# SCH_IoTNode_2025-08-17.net
KiCad netlist of a schematic drawn in EasyEDA
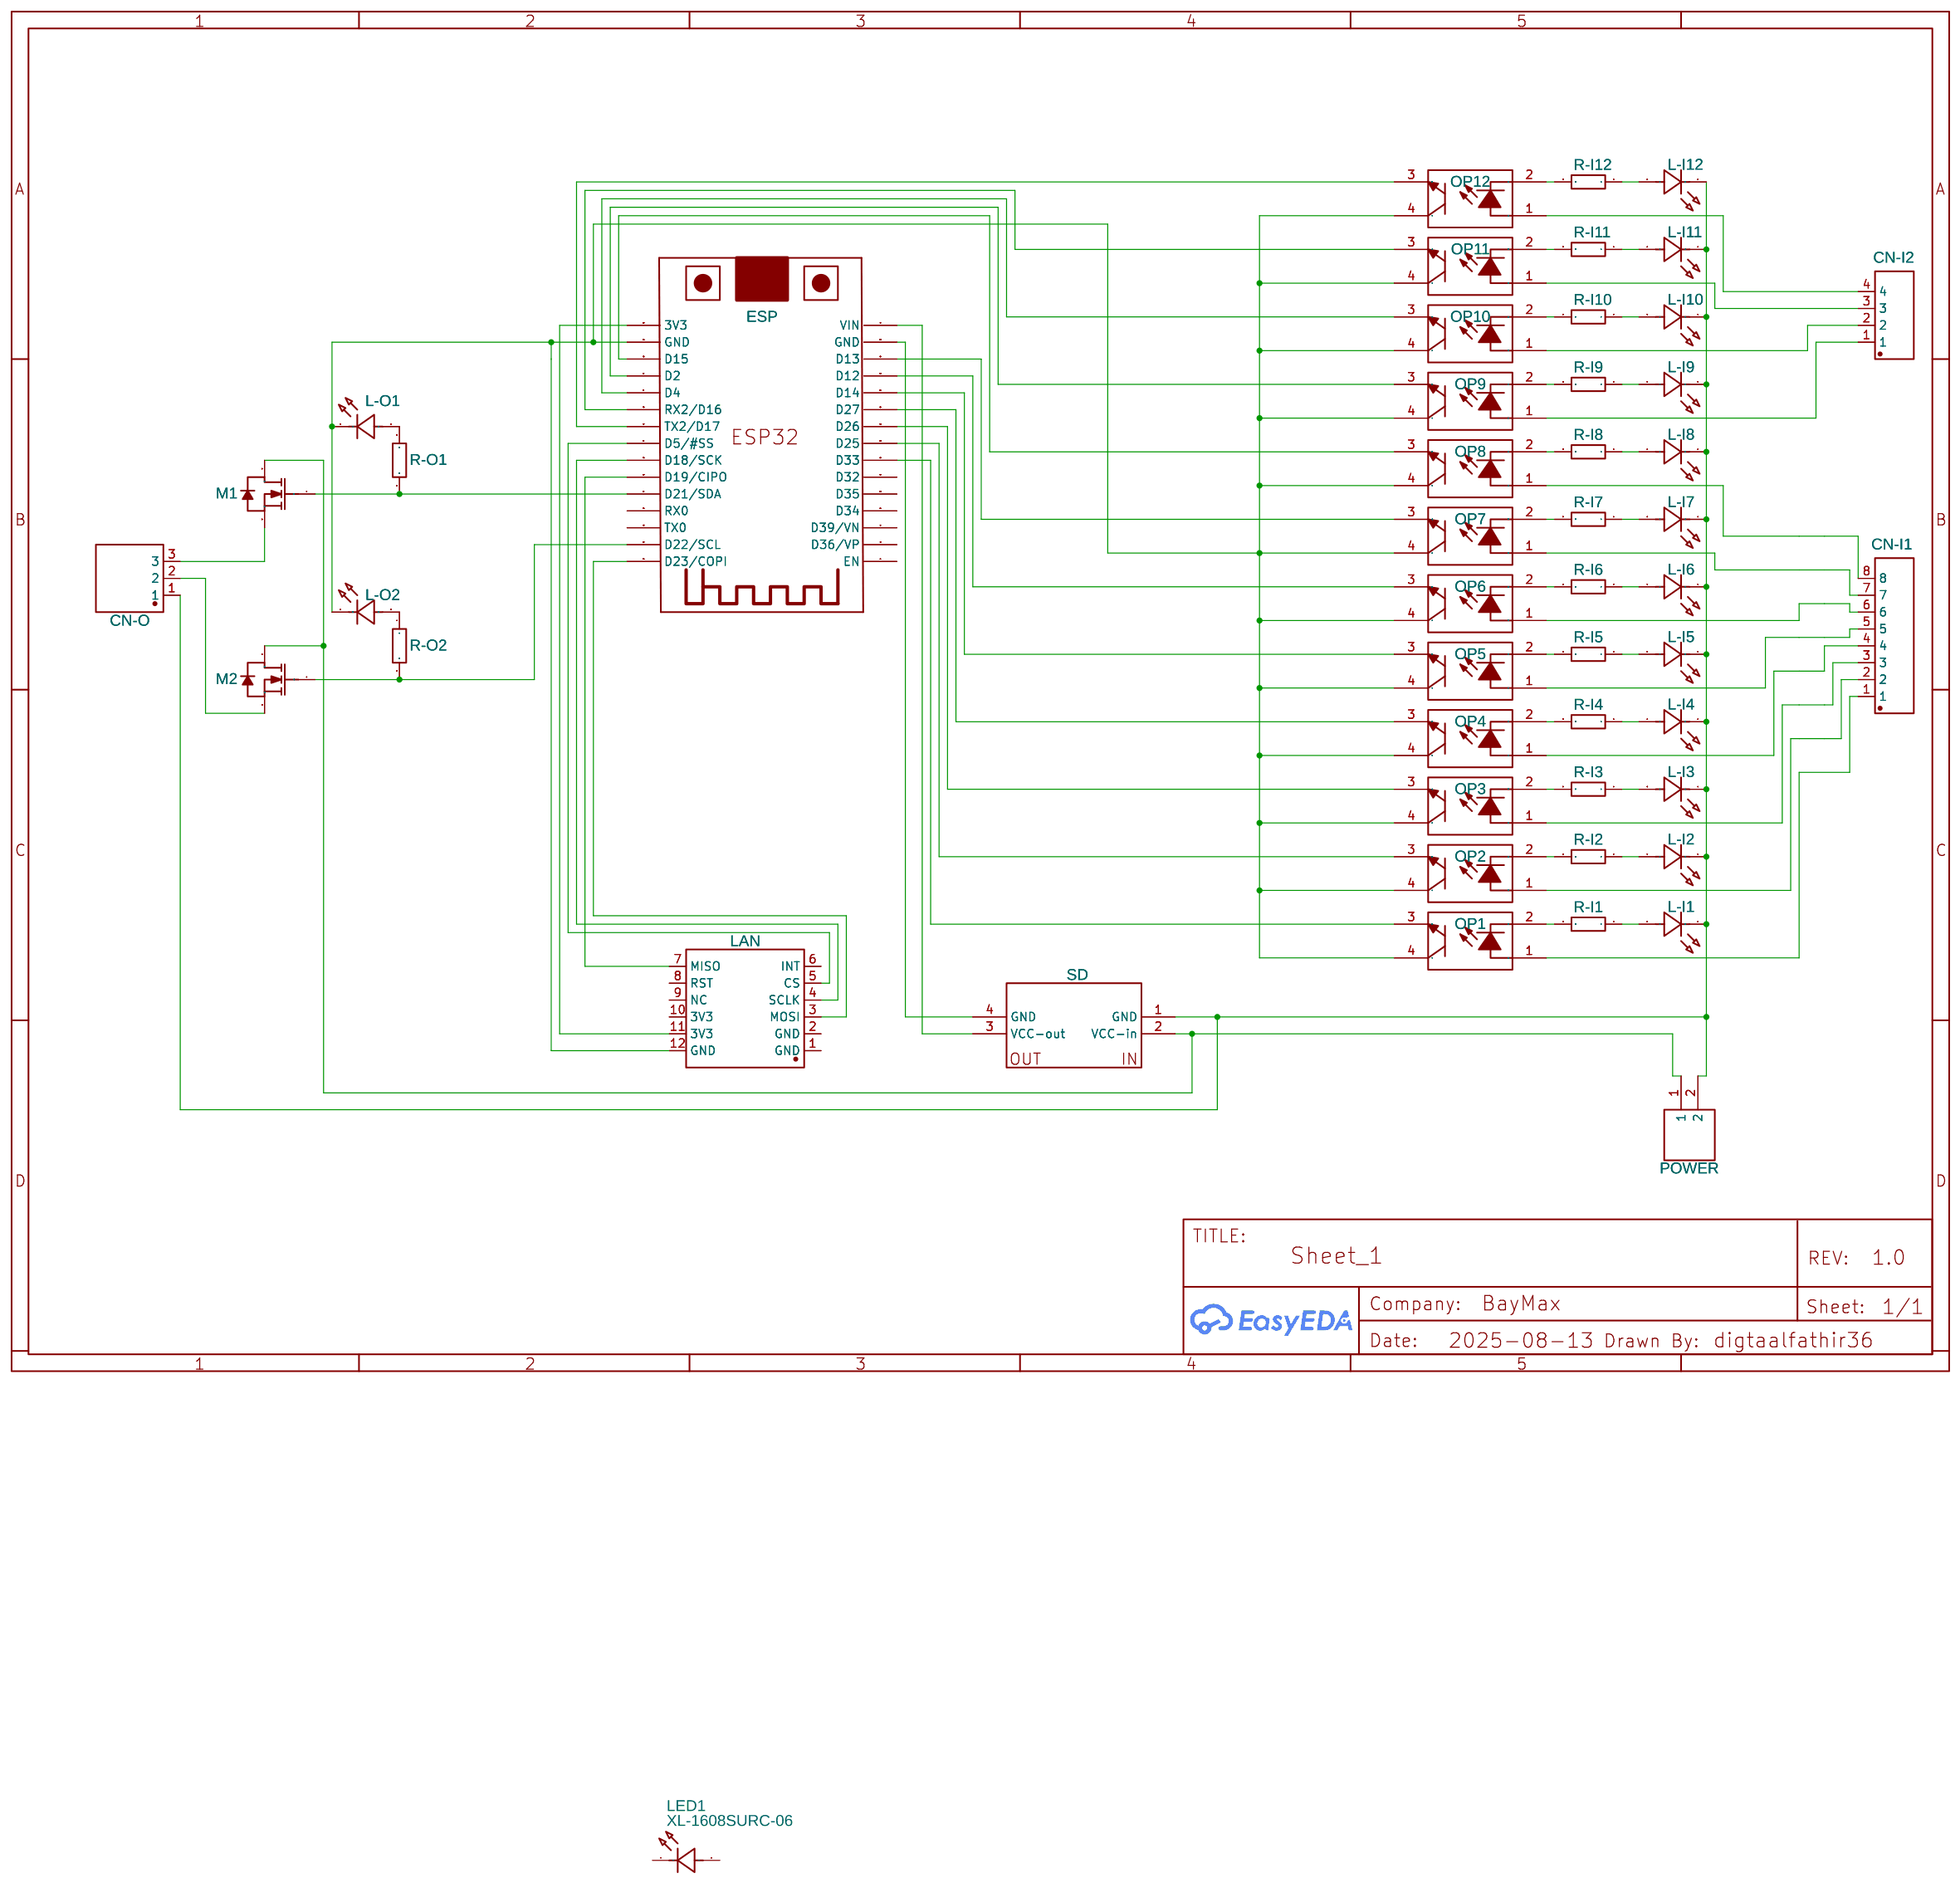
[diagram p0: schematic sheet]

(export (version "E")
  (design (tool "Eeschema 10.0.6"))
  (components
    (comp (ref "CN-I1")
      (value "WJ2EDGRC-5.08-8P")
      (fields (field (name "Manufacturer") "KANGNEX(康奈克斯电气)"))
      (libsource (lib "") (part "WJ2EDGRC-5.08-8P"))
    )
    (comp (ref "CN-I2")
      (value "WJ2EDGRC-5.08-4P")
      (fields (field (name "Manufacturer") "KANGNEX(康奈克斯电气)"))
      (libsource (lib "") (part "WJ2EDGRC-5.08-4P"))
    )
    (comp (ref "CN-O")
      (value "WJ2EDGRC-5.08-3P_C8377")
      (fields
        (field (name "Manufacturer Part") "WJ2EDGRC-5.08-3P")
        (field (name "Manufacturer") "KANGNEX(康奈克斯电气)")
      )
      (libsource (lib "") (part "WJ2EDGRC-5.08-3P_C8377"))
    )
    (comp (ref "ESP") (value "ESP32_30PIN_TESTccccccc") (libsource (lib "") (part "ESP32-DEVKIT-V1-30PIN")))
    (comp (ref "L-I1")
      (value "XL-1608SURC-06")
      (fields (field (name "Manufacturer") "XINGLIGHT(成兴光)"))
      (libsource (lib "") (part "XL-1608SURC-06"))
    )
    (comp (ref "L-I2")
      (value "XL-1608SURC-06")
      (fields (field (name "Manufacturer") "XINGLIGHT(成兴光)"))
      (libsource (lib "") (part "XL-1608SURC-06"))
    )
    (comp (ref "L-I3")
      (value "XL-1608SURC-06")
      (fields (field (name "Manufacturer") "XINGLIGHT(成兴光)"))
      (libsource (lib "") (part "XL-1608SURC-06"))
    )
    (comp (ref "L-I4")
      (value "XL-1608SURC-06")
      (fields (field (name "Manufacturer") "XINGLIGHT(成兴光)"))
      (libsource (lib "") (part "XL-1608SURC-06"))
    )
    (comp (ref "L-I5")
      (value "XL-1608SURC-06")
      (fields (field (name "Manufacturer") "XINGLIGHT(成兴光)"))
      (libsource (lib "") (part "XL-1608SURC-06"))
    )
    (comp (ref "L-I6")
      (value "XL-1608SURC-06")
      (fields (field (name "Manufacturer") "XINGLIGHT(成兴光)"))
      (libsource (lib "") (part "XL-1608SURC-06"))
    )
    (comp (ref "L-I7")
      (value "XL-1608SURC-06")
      (fields (field (name "Manufacturer") "XINGLIGHT(成兴光)"))
      (libsource (lib "") (part "XL-1608SURC-06"))
    )
    (comp (ref "L-I8")
      (value "XL-1608SURC-06")
      (fields (field (name "Manufacturer") "XINGLIGHT(成兴光)"))
      (libsource (lib "") (part "XL-1608SURC-06"))
    )
    (comp (ref "L-I9")
      (value "XL-1608SURC-06")
      (fields (field (name "Manufacturer") "XINGLIGHT(成兴光)"))
      (libsource (lib "") (part "XL-1608SURC-06"))
    )
    (comp (ref "L-I10")
      (value "XL-1608SURC-06")
      (fields (field (name "Manufacturer") "XINGLIGHT(成兴光)"))
      (libsource (lib "") (part "XL-1608SURC-06"))
    )
    (comp (ref "L-I11")
      (value "XL-1608SURC-06")
      (fields (field (name "Manufacturer") "XINGLIGHT(成兴光)"))
      (libsource (lib "") (part "XL-1608SURC-06"))
    )
    (comp (ref "L-I12")
      (value "XL-1608SURC-06")
      (fields (field (name "Manufacturer") "XINGLIGHT(成兴光)"))
      (libsource (lib "") (part "XL-1608SURC-06"))
    )
    (comp (ref "L-O1")
      (value "XL-1608SURC-06")
      (fields (field (name "Manufacturer") "XINGLIGHT(成兴光)"))
      (libsource (lib "") (part "XL-1608SURC-06_1"))
    )
    (comp (ref "L-O2")
      (value "XL-1608SURC-06")
      (fields (field (name "Manufacturer") "XINGLIGHT(成兴光)"))
      (libsource (lib "") (part "XL-1608SURC-06_1"))
    )
    (comp (ref "LAN") (value "W5500_MODULE") (libsource (lib "") (part "W5500_MODULE")))
    (comp (ref "LED1")
      (value "XL-1608SURC-06")
      (fields (field (name "Manufacturer") "XINGLIGHT(成兴光)"))
      (libsource (lib "") (part "XL-1608SURC-06_2"))
    )
    (comp (ref "M1")
      (value "IRF520_C3280676")
      (fields (field (name "Manufacturer Part") "IRF520") (field (name "Manufacturer") "HARRIS(哈利斯)"))
      (libsource (lib "") (part "IRF520_C3280676"))
    )
    (comp (ref "M2")
      (value "IRF520_C3280676")
      (fields (field (name "Manufacturer Part") "IRF520") (field (name "Manufacturer") "HARRIS(哈利斯)"))
      (libsource (lib "") (part "IRF520_C3280676"))
    )
    (comp (ref "OP1")
      (value "PC817X3NSZW")
      (fields (field (name "Manufacturer") "SHARP(夏普)"))
      (libsource (lib "") (part "PC817X3NSZW"))
    )
    (comp (ref "OP2")
      (value "PC817X3NSZW")
      (fields (field (name "Manufacturer") "SHARP(夏普)"))
      (libsource (lib "") (part "PC817X3NSZW"))
    )
    (comp (ref "OP3")
      (value "PC817X3NSZW")
      (fields (field (name "Manufacturer") "SHARP(夏普)"))
      (libsource (lib "") (part "PC817X3NSZW"))
    )
    (comp (ref "OP4")
      (value "PC817X3NSZW")
      (fields (field (name "Manufacturer") "SHARP(夏普)"))
      (libsource (lib "") (part "PC817X3NSZW"))
    )
    (comp (ref "OP5")
      (value "PC817X3NSZW")
      (fields (field (name "Manufacturer") "SHARP(夏普)"))
      (libsource (lib "") (part "PC817X3NSZW"))
    )
    (comp (ref "OP6")
      (value "PC817X3NSZW")
      (fields (field (name "Manufacturer") "SHARP(夏普)"))
      (libsource (lib "") (part "PC817X3NSZW"))
    )
    (comp (ref "OP7")
      (value "PC817X3NSZW")
      (fields (field (name "Manufacturer") "SHARP(夏普)"))
      (libsource (lib "") (part "PC817X3NSZW"))
    )
    (comp (ref "OP8")
      (value "PC817X3NSZW")
      (fields (field (name "Manufacturer") "SHARP(夏普)"))
      (libsource (lib "") (part "PC817X3NSZW"))
    )
    (comp (ref "OP9")
      (value "PC817X3NSZW")
      (fields (field (name "Manufacturer") "SHARP(夏普)"))
      (libsource (lib "") (part "PC817X3NSZW"))
    )
    (comp (ref "OP10")
      (value "PC817X3NSZW")
      (fields (field (name "Manufacturer") "SHARP(夏普)"))
      (libsource (lib "") (part "PC817X3NSZW"))
    )
    (comp (ref "OP11")
      (value "PC817X3NSZW")
      (fields (field (name "Manufacturer") "SHARP(夏普)"))
      (libsource (lib "") (part "PC817X3NSZW"))
    )
    (comp (ref "OP12")
      (value "PC817X3NSZW")
      (fields (field (name "Manufacturer") "SHARP(夏普)"))
      (libsource (lib "") (part "PC817X3NSZW"))
    )
    (comp (ref "POWER")
      (value "WJ2EDGRC-5.08-2P")
      (fields (field (name "Manufacturer") "KANGNEX(康奈克斯电气)"))
      (libsource (lib "") (part "WJ2EDGRC-5.08-2P"))
    )
    (comp (ref "R-I1")
      (value "10kΩ")
      (fields (field (name "Manufacturer Part") "RC0603FR-0710KL") (field (name "Manufacturer") "YAGEO(国巨)"))
      (libsource (lib "") (part "RC0603FR-0710KL_1"))
    )
    (comp (ref "R-I2")
      (value "10kΩ")
      (fields (field (name "Manufacturer Part") "RC0603FR-0710KL") (field (name "Manufacturer") "YAGEO(国巨)"))
      (libsource (lib "") (part "RC0603FR-0710KL_1"))
    )
    (comp (ref "R-I3")
      (value "10kΩ")
      (fields (field (name "Manufacturer Part") "RC0603FR-0710KL") (field (name "Manufacturer") "YAGEO(国巨)"))
      (libsource (lib "") (part "RC0603FR-0710KL_1"))
    )
    (comp (ref "R-I4")
      (value "10kΩ")
      (fields (field (name "Manufacturer Part") "RC0603FR-0710KL") (field (name "Manufacturer") "YAGEO(国巨)"))
      (libsource (lib "") (part "RC0603FR-0710KL_1"))
    )
    (comp (ref "R-I5")
      (value "10kΩ")
      (fields (field (name "Manufacturer Part") "RC0603FR-0710KL") (field (name "Manufacturer") "YAGEO(国巨)"))
      (libsource (lib "") (part "RC0603FR-0710KL_1"))
    )
    (comp (ref "R-I6")
      (value "10kΩ")
      (fields (field (name "Manufacturer Part") "RC0603FR-0710KL") (field (name "Manufacturer") "YAGEO(国巨)"))
      (libsource (lib "") (part "RC0603FR-0710KL_1"))
    )
    (comp (ref "R-I7")
      (value "10kΩ")
      (fields (field (name "Manufacturer Part") "RC0603FR-0710KL") (field (name "Manufacturer") "YAGEO(国巨)"))
      (libsource (lib "") (part "RC0603FR-0710KL_1"))
    )
    (comp (ref "R-I8")
      (value "10kΩ")
      (fields (field (name "Manufacturer Part") "RC0603FR-0710KL") (field (name "Manufacturer") "YAGEO(国巨)"))
      (libsource (lib "") (part "RC0603FR-0710KL_1"))
    )
    (comp (ref "R-I9")
      (value "10kΩ")
      (fields (field (name "Manufacturer Part") "RC0603FR-0710KL") (field (name "Manufacturer") "YAGEO(国巨)"))
      (libsource (lib "") (part "RC0603FR-0710KL_1"))
    )
    (comp (ref "R-I10")
      (value "10kΩ")
      (fields (field (name "Manufacturer Part") "RC0603FR-0710KL") (field (name "Manufacturer") "YAGEO(国巨)"))
      (libsource (lib "") (part "RC0603FR-0710KL_1"))
    )
    (comp (ref "R-I11")
      (value "10kΩ")
      (fields (field (name "Manufacturer Part") "RC0603FR-0710KL") (field (name "Manufacturer") "YAGEO(国巨)"))
      (libsource (lib "") (part "RC0603FR-0710KL_1"))
    )
    (comp (ref "R-I12")
      (value "10kΩ")
      (fields (field (name "Manufacturer Part") "RC0603FR-0710KL") (field (name "Manufacturer") "YAGEO(国巨)"))
      (libsource (lib "") (part "RC0603FR-0710KL_1"))
    )
    (comp (ref "R-O1")
      (value "10kΩ")
      (fields (field (name "Manufacturer Part") "RC0603FR-0710KL") (field (name "Manufacturer") "YAGEO(国巨)"))
      (libsource (lib "") (part "RC0603FR-0710KL"))
    )
    (comp (ref "R-O2")
      (value "10kΩ")
      (fields (field (name "Manufacturer Part") "RC0603FR-0710KL") (field (name "Manufacturer") "YAGEO(国巨)"))
      (libsource (lib "") (part "RC0603FR-0710KL"))
    )
    (comp (ref "SD")
      (value "MP1584 step down Module")
      (fields (field (name "Manufacturer Part") "MP1584 Module"))
      (libsource (lib "") (part "MP1584 step down Module"))
    )
  )
  (nets
    (net (code "1") (name "Net-(CN-I1-Pad1)") (class "Default")
      (node (ref "CN-I1") (pin "1") (pinfunction "1_1") (pintype "unspecified"))
      (node (ref "OP1") (pin "1") (pinfunction "1_1") (pintype "unspecified"))
    )
    (net (code "2") (name "Net-(CN-I1-Pad2)") (class "Default")
      (node (ref "CN-I1") (pin "2") (pinfunction "2_2") (pintype "unspecified"))
      (node (ref "OP2") (pin "1") (pinfunction "1_1") (pintype "unspecified"))
    )
    (net (code "3") (name "Net-(CN-I1-Pad3)") (class "Default")
      (node (ref "CN-I1") (pin "3") (pinfunction "3_3") (pintype "unspecified"))
      (node (ref "OP3") (pin "1") (pinfunction "1_1") (pintype "unspecified"))
    )
    (net (code "4") (name "Net-(CN-I1-Pad4)") (class "Default")
      (node (ref "CN-I1") (pin "4") (pinfunction "4_4") (pintype "unspecified"))
      (node (ref "OP4") (pin "1") (pinfunction "1_1") (pintype "unspecified"))
    )
    (net (code "5") (name "Net-(CN-I1-Pad5)") (class "Default")
      (node (ref "CN-I1") (pin "5") (pinfunction "5_5") (pintype "unspecified"))
      (node (ref "OP5") (pin "1") (pinfunction "1_1") (pintype "unspecified"))
    )
    (net (code "6") (name "Net-(CN-I1-Pad6)") (class "Default")
      (node (ref "CN-I1") (pin "6") (pinfunction "6_6") (pintype "unspecified"))
      (node (ref "OP6") (pin "1") (pinfunction "1_1") (pintype "unspecified"))
    )
    (net (code "7") (name "Net-(CN-I1-Pad7)") (class "Default")
      (node (ref "CN-I1") (pin "7") (pinfunction "7_7") (pintype "unspecified"))
      (node (ref "OP7") (pin "1") (pinfunction "1_1") (pintype "unspecified"))
    )
    (net (code "8") (name "Net-(CN-I1-Pad8)") (class "Default")
      (node (ref "CN-I1") (pin "8") (pinfunction "8_8") (pintype "unspecified"))
      (node (ref "OP8") (pin "1") (pinfunction "1_1") (pintype "unspecified"))
    )
    (net (code "9") (name "Net-(CN-I2-Pad1)") (class "Default")
      (node (ref "CN-I2") (pin "1") (pinfunction "1_1") (pintype "unspecified"))
      (node (ref "OP9") (pin "1") (pinfunction "1_1") (pintype "unspecified"))
    )
    (net (code "10") (name "Net-(CN-I2-Pad2)") (class "Default")
      (node (ref "CN-I2") (pin "2") (pinfunction "2_2") (pintype "unspecified"))
      (node (ref "OP10") (pin "1") (pinfunction "1_1") (pintype "unspecified"))
    )
    (net (code "11") (name "Net-(CN-I2-Pad3)") (class "Default")
      (node (ref "CN-I2") (pin "3") (pinfunction "3_3") (pintype "unspecified"))
      (node (ref "OP11") (pin "1") (pinfunction "1_1") (pintype "unspecified"))
    )
    (net (code "12") (name "Net-(CN-I2-Pad4)") (class "Default")
      (node (ref "CN-I2") (pin "4") (pinfunction "4_4") (pintype "unspecified"))
      (node (ref "OP12") (pin "1") (pinfunction "1_1") (pintype "unspecified"))
    )
    (net (code "13") (name "Net-(ESP-D5{slash}#SS)") (class "Default")
      (node (ref "ESP") (pin "D5") (pinfunction "D5/#SS_D5") (pintype "unspecified"))
      (node (ref "LAN") (pin "5") (pinfunction "CS_5") (pintype "unspecified"))
    )
    (net (code "14") (name "Net-(ESP-D18{slash}SCK)") (class "Default")
      (node (ref "ESP") (pin "D18") (pinfunction "D18/SCK_D18") (pintype "unspecified"))
      (node (ref "LAN") (pin "4") (pinfunction "SCLK_4") (pintype "unspecified"))
    )
    (net (code "15") (name "Net-(ESP-D19{slash}CIPO)") (class "Default")
      (node (ref "ESP") (pin "D19") (pinfunction "D19/CIPO_D19") (pintype "unspecified"))
      (node (ref "LAN") (pin "7") (pinfunction "MISO_7") (pintype "unspecified"))
    )
    (net (code "16") (name "Net-(ESP-D21{slash}SDA)") (class "Default")
      (node (ref "ESP") (pin "D21") (pinfunction "D21/SDA_D21") (pintype "unspecified"))
      (node (ref "M1") (pin "1") (pinfunction "G_1") (pintype "unspecified"))
      (node (ref "R-O1") (pin "2") (pinfunction "2_2") (pintype "input"))
    )
    (net (code "17") (name "Net-(ESP-D22{slash}SCL)") (class "Default")
      (node (ref "ESP") (pin "D22") (pinfunction "D22/SCL_D22") (pintype "unspecified"))
      (node (ref "M2") (pin "1") (pinfunction "G_1") (pintype "unspecified"))
      (node (ref "R-O2") (pin "2") (pinfunction "2_2") (pintype "input"))
    )
    (net (code "18") (name "Net-(ESP-D23{slash}COPI)") (class "Default")
      (node (ref "ESP") (pin "D23") (pinfunction "D23/COPI_D23") (pintype "unspecified"))
      (node (ref "LAN") (pin "3") (pinfunction "MOSI_3") (pintype "unspecified"))
    )
    (net (code "19") (name "Net-(ESP-GND-PadGND2)") (class "Default")
      (node (ref "ESP") (pin "GND2") (pinfunction "GND_GND2") (pintype "unspecified"))
      (node (ref "SD") (pin "4") (pinfunction "GND_4") (pintype "unspecified"))
    )
    (net (code "20") (name "Net-(ESP-Pad3V3)") (class "Default")
      (node (ref "ESP") (pin "3V3") (pinfunction "3V3_3V3") (pintype "unspecified"))
      (node (ref "LAN") (pin "11") (pinfunction "3V3_11") (pintype "unspecified"))
    )
    (net (code "21") (name "Net-(ESP-PadD2)") (class "Default")
      (node (ref "ESP") (pin "D2") (pinfunction "D2_D2") (pintype "unspecified"))
      (node (ref "OP9") (pin "3") (pinfunction "3_3") (pintype "unspecified"))
    )
    (net (code "22") (name "Net-(ESP-PadD4)") (class "Default")
      (node (ref "ESP") (pin "D4") (pinfunction "D4_D4") (pintype "unspecified"))
      (node (ref "OP10") (pin "3") (pinfunction "3_3") (pintype "unspecified"))
    )
    (net (code "23") (name "Net-(ESP-PadD12)") (class "Default")
      (node (ref "ESP") (pin "D12") (pinfunction "D12_D12") (pintype "unspecified"))
      (node (ref "OP6") (pin "3") (pinfunction "3_3") (pintype "unspecified"))
    )
    (net (code "24") (name "Net-(ESP-PadD13)") (class "Default")
      (node (ref "ESP") (pin "D13") (pinfunction "D13_D13") (pintype "unspecified"))
      (node (ref "OP7") (pin "3") (pinfunction "3_3") (pintype "unspecified"))
    )
    (net (code "25") (name "Net-(ESP-PadD14)") (class "Default")
      (node (ref "ESP") (pin "D14") (pinfunction "D14_D14") (pintype "unspecified"))
      (node (ref "OP5") (pin "3") (pinfunction "3_3") (pintype "unspecified"))
    )
    (net (code "26") (name "Net-(ESP-PadD15)") (class "Default")
      (node (ref "ESP") (pin "D15") (pinfunction "D15_D15") (pintype "unspecified"))
      (node (ref "OP8") (pin "3") (pinfunction "3_3") (pintype "unspecified"))
    )
    (net (code "27") (name "Net-(ESP-PadD25)") (class "Default")
      (node (ref "ESP") (pin "D25") (pinfunction "D25_D25") (pintype "unspecified"))
      (node (ref "OP2") (pin "3") (pinfunction "3_3") (pintype "unspecified"))
    )
    (net (code "28") (name "Net-(ESP-PadD26)") (class "Default")
      (node (ref "ESP") (pin "D26") (pinfunction "D26_D26") (pintype "unspecified"))
      (node (ref "OP3") (pin "3") (pinfunction "3_3") (pintype "unspecified"))
    )
    (net (code "29") (name "Net-(ESP-PadD27)") (class "Default")
      (node (ref "ESP") (pin "D27") (pinfunction "D27_D27") (pintype "unspecified"))
      (node (ref "OP4") (pin "3") (pinfunction "3_3") (pintype "unspecified"))
    )
    (net (code "30") (name "Net-(ESP-PadD33)") (class "Default")
      (node (ref "ESP") (pin "D33") (pinfunction "D33_D33") (pintype "unspecified"))
      (node (ref "OP1") (pin "3") (pinfunction "3_3") (pintype "unspecified"))
    )
    (net (code "31") (name "Net-(ESP-RX2{slash}D16)") (class "Default")
      (node (ref "ESP") (pin "RX2") (pinfunction "RX2/D16_RX2") (pintype "unspecified"))
      (node (ref "OP11") (pin "3") (pinfunction "3_3") (pintype "unspecified"))
    )
    (net (code "32") (name "Net-(ESP-TX2{slash}D17)") (class "Default")
      (node (ref "ESP") (pin "TX2") (pinfunction "TX2/D17_TX2") (pintype "unspecified"))
      (node (ref "OP12") (pin "3") (pinfunction "3_3") (pintype "unspecified"))
    )
    (net (code "33") (name "Net-(L-I1-A)") (class "Default")
      (node (ref "L-I1") (pin "2") (pinfunction "A_2") (pintype "unspecified"))
      (node (ref "R-I1") (pin "1") (pinfunction "1_1") (pintype "input"))
    )
    (net (code "34") (name "Net-(L-I1-K)") (class "Default")
      (node (ref "CN-O") (pin "1") (pinfunction "1_1") (pintype "unspecified"))
      (node (ref "L-I1") (pin "1") (pinfunction "K_1") (pintype "unspecified"))
      (node (ref "L-I10") (pin "1") (pinfunction "K_1") (pintype "unspecified"))
      (node (ref "L-I11") (pin "1") (pinfunction "K_1") (pintype "unspecified"))
      (node (ref "L-I12") (pin "1") (pinfunction "K_1") (pintype "unspecified"))
      (node (ref "L-I2") (pin "1") (pinfunction "K_1") (pintype "unspecified"))
      (node (ref "L-I3") (pin "1") (pinfunction "K_1") (pintype "unspecified"))
      (node (ref "L-I4") (pin "1") (pinfunction "K_1") (pintype "unspecified"))
      (node (ref "L-I5") (pin "1") (pinfunction "K_1") (pintype "unspecified"))
      (node (ref "L-I6") (pin "1") (pinfunction "K_1") (pintype "unspecified"))
      (node (ref "L-I7") (pin "1") (pinfunction "K_1") (pintype "unspecified"))
      (node (ref "L-I8") (pin "1") (pinfunction "K_1") (pintype "unspecified"))
      (node (ref "L-I9") (pin "1") (pinfunction "K_1") (pintype "unspecified"))
      (node (ref "POWER") (pin "2") (pinfunction "2_2") (pintype "unspecified"))
      (node (ref "SD") (pin "1") (pinfunction "GND_1") (pintype "unspecified"))
    )
    (net (code "35") (name "Net-(L-I2-A)") (class "Default")
      (node (ref "L-I2") (pin "2") (pinfunction "A_2") (pintype "unspecified"))
      (node (ref "R-I2") (pin "1") (pinfunction "1_1") (pintype "input"))
    )
    (net (code "36") (name "Net-(L-I3-A)") (class "Default")
      (node (ref "L-I3") (pin "2") (pinfunction "A_2") (pintype "unspecified"))
      (node (ref "R-I3") (pin "1") (pinfunction "1_1") (pintype "input"))
    )
    (net (code "37") (name "Net-(L-I4-A)") (class "Default")
      (node (ref "L-I4") (pin "2") (pinfunction "A_2") (pintype "unspecified"))
      (node (ref "R-I4") (pin "1") (pinfunction "1_1") (pintype "input"))
    )
    (net (code "38") (name "Net-(L-I5-A)") (class "Default")
      (node (ref "L-I5") (pin "2") (pinfunction "A_2") (pintype "unspecified"))
      (node (ref "R-I5") (pin "1") (pinfunction "1_1") (pintype "input"))
    )
    (net (code "39") (name "Net-(L-I6-A)") (class "Default")
      (node (ref "L-I6") (pin "2") (pinfunction "A_2") (pintype "unspecified"))
      (node (ref "R-I6") (pin "1") (pinfunction "1_1") (pintype "input"))
    )
    (net (code "40") (name "Net-(L-I7-A)") (class "Default")
      (node (ref "L-I7") (pin "2") (pinfunction "A_2") (pintype "unspecified"))
      (node (ref "R-I7") (pin "1") (pinfunction "1_1") (pintype "input"))
    )
    (net (code "41") (name "Net-(L-I8-A)") (class "Default")
      (node (ref "L-I8") (pin "2") (pinfunction "A_2") (pintype "unspecified"))
      (node (ref "R-I8") (pin "1") (pinfunction "1_1") (pintype "input"))
    )
    (net (code "42") (name "Net-(L-I9-A)") (class "Default")
      (node (ref "L-I9") (pin "2") (pinfunction "A_2") (pintype "unspecified"))
      (node (ref "R-I9") (pin "1") (pinfunction "1_1") (pintype "input"))
    )
    (net (code "43") (name "Net-(L-I10-A)") (class "Default")
      (node (ref "L-I10") (pin "2") (pinfunction "A_2") (pintype "unspecified"))
      (node (ref "R-I10") (pin "1") (pinfunction "1_1") (pintype "input"))
    )
    (net (code "44") (name "Net-(L-I11-A)") (class "Default")
      (node (ref "L-I11") (pin "2") (pinfunction "A_2") (pintype "unspecified"))
      (node (ref "R-I11") (pin "1") (pinfunction "1_1") (pintype "input"))
    )
    (net (code "45") (name "Net-(L-I12-A)") (class "Default")
      (node (ref "L-I12") (pin "2") (pinfunction "A_2") (pintype "unspecified"))
      (node (ref "R-I12") (pin "1") (pinfunction "1_1") (pintype "input"))
    )
    (net (code "46") (name "Net-(L-O1-A)") (class "Default")
      (node (ref "L-O1") (pin "2") (pinfunction "A_2") (pintype "unspecified"))
      (node (ref "R-O1") (pin "1") (pinfunction "1_1") (pintype "input"))
    )
    (net (code "47") (name "Net-(L-O1-K)") (class "Default")
      (node (ref "ESP") (pin "GND") (pinfunction "GND_GND") (pintype "unspecified"))
      (node (ref "L-O1") (pin "1") (pinfunction "K_1") (pintype "unspecified"))
      (node (ref "L-O2") (pin "1") (pinfunction "K_1") (pintype "unspecified"))
      (node (ref "LAN") (pin "12") (pinfunction "GND_12") (pintype "unspecified"))
      (node (ref "OP1") (pin "4") (pinfunction "4_4") (pintype "unspecified"))
      (node (ref "OP10") (pin "4") (pinfunction "4_4") (pintype "unspecified"))
      (node (ref "OP11") (pin "4") (pinfunction "4_4") (pintype "unspecified"))
      (node (ref "OP12") (pin "4") (pinfunction "4_4") (pintype "unspecified"))
      (node (ref "OP2") (pin "4") (pinfunction "4_4") (pintype "unspecified"))
      (node (ref "OP3") (pin "4") (pinfunction "4_4") (pintype "unspecified"))
      (node (ref "OP4") (pin "4") (pinfunction "4_4") (pintype "unspecified"))
      (node (ref "OP5") (pin "4") (pinfunction "4_4") (pintype "unspecified"))
      (node (ref "OP6") (pin "4") (pinfunction "4_4") (pintype "unspecified"))
      (node (ref "OP7") (pin "4") (pinfunction "4_4") (pintype "unspecified"))
      (node (ref "OP8") (pin "4") (pinfunction "4_4") (pintype "unspecified"))
      (node (ref "OP9") (pin "4") (pinfunction "4_4") (pintype "unspecified"))
    )
    (net (code "48") (name "Net-(L-O2-A)") (class "Default")
      (node (ref "L-O2") (pin "2") (pinfunction "A_2") (pintype "unspecified"))
      (node (ref "R-O2") (pin "1") (pinfunction "1_1") (pintype "input"))
    )
    (net (code "49") (name "Net-(M1-D)") (class "Default")
      (node (ref "M1") (pin "2") (pinfunction "D_2") (pintype "unspecified"))
      (node (ref "M2") (pin "2") (pinfunction "D_2") (pintype "unspecified"))
      (node (ref "POWER") (pin "1") (pinfunction "1_1") (pintype "unspecified"))
      (node (ref "SD") (pin "2") (pinfunction "VCC-in_2") (pintype "unspecified"))
    )
    (net (code "50") (name "Net-(M1-S)") (class "Default")
      (node (ref "CN-O") (pin "3") (pinfunction "3_3") (pintype "unspecified"))
      (node (ref "M1") (pin "3") (pinfunction "S_3") (pintype "unspecified"))
    )
    (net (code "51") (name "Net-(M2-S)") (class "Default")
      (node (ref "CN-O") (pin "2") (pinfunction "2_2") (pintype "unspecified"))
      (node (ref "M2") (pin "3") (pinfunction "S_3") (pintype "unspecified"))
    )
    (net (code "52") (name "Net-(OP1-Pad2)") (class "Default")
      (node (ref "OP1") (pin "2") (pinfunction "2_2") (pintype "unspecified"))
      (node (ref "R-I1") (pin "2") (pinfunction "2_2") (pintype "input"))
    )
    (net (code "53") (name "Net-(OP2-Pad2)") (class "Default")
      (node (ref "OP2") (pin "2") (pinfunction "2_2") (pintype "unspecified"))
      (node (ref "R-I2") (pin "2") (pinfunction "2_2") (pintype "input"))
    )
    (net (code "54") (name "Net-(OP3-Pad2)") (class "Default")
      (node (ref "OP3") (pin "2") (pinfunction "2_2") (pintype "unspecified"))
      (node (ref "R-I3") (pin "2") (pinfunction "2_2") (pintype "input"))
    )
    (net (code "55") (name "Net-(OP4-Pad2)") (class "Default")
      (node (ref "OP4") (pin "2") (pinfunction "2_2") (pintype "unspecified"))
      (node (ref "R-I4") (pin "2") (pinfunction "2_2") (pintype "input"))
    )
    (net (code "56") (name "Net-(OP5-Pad2)") (class "Default")
      (node (ref "OP5") (pin "2") (pinfunction "2_2") (pintype "unspecified"))
      (node (ref "R-I5") (pin "2") (pinfunction "2_2") (pintype "input"))
    )
    (net (code "57") (name "Net-(OP6-Pad2)") (class "Default")
      (node (ref "OP6") (pin "2") (pinfunction "2_2") (pintype "unspecified"))
      (node (ref "R-I6") (pin "2") (pinfunction "2_2") (pintype "input"))
    )
    (net (code "58") (name "Net-(OP7-Pad2)") (class "Default")
      (node (ref "OP7") (pin "2") (pinfunction "2_2") (pintype "unspecified"))
      (node (ref "R-I7") (pin "2") (pinfunction "2_2") (pintype "input"))
    )
    (net (code "59") (name "Net-(OP8-Pad2)") (class "Default")
      (node (ref "OP8") (pin "2") (pinfunction "2_2") (pintype "unspecified"))
      (node (ref "R-I8") (pin "2") (pinfunction "2_2") (pintype "input"))
    )
    (net (code "60") (name "Net-(OP9-Pad2)") (class "Default")
      (node (ref "OP9") (pin "2") (pinfunction "2_2") (pintype "unspecified"))
      (node (ref "R-I9") (pin "2") (pinfunction "2_2") (pintype "input"))
    )
    (net (code "61") (name "Net-(OP10-Pad2)") (class "Default")
      (node (ref "OP10") (pin "2") (pinfunction "2_2") (pintype "unspecified"))
      (node (ref "R-I10") (pin "2") (pinfunction "2_2") (pintype "input"))
    )
    (net (code "62") (name "Net-(OP11-Pad2)") (class "Default")
      (node (ref "OP11") (pin "2") (pinfunction "2_2") (pintype "unspecified"))
      (node (ref "R-I11") (pin "2") (pinfunction "2_2") (pintype "input"))
    )
    (net (code "63") (name "Net-(OP12-Pad2)") (class "Default")
      (node (ref "OP12") (pin "2") (pinfunction "2_2") (pintype "unspecified"))
      (node (ref "R-I12") (pin "2") (pinfunction "2_2") (pintype "input"))
    )
    (net (code "64") (name "Net-(SD-VCC-out)") (class "Default")
      (node (ref "ESP") (pin "VIN") (pinfunction "VIN_VIN") (pintype "unspecified"))
      (node (ref "SD") (pin "3") (pinfunction "VCC-out_3") (pintype "unspecified"))
    )
    (net (code "65") (name "unconnected-(ESP-D36{slash}VP-PadVP)") (class "Default")
      (node (ref "ESP") (pin "VP") (pinfunction "D36/VP_VP") (pintype "unspecified"))
    )
    (net (code "66") (name "unconnected-(ESP-D39{slash}VN-PadVN)") (class "Default")
      (node (ref "ESP") (pin "VN") (pinfunction "D39/VN_VN") (pintype "unspecified"))
    )
    (net (code "67") (name "unconnected-(ESP-PadD32)") (class "Default")
      (node (ref "ESP") (pin "D32") (pinfunction "D32_D32") (pintype "unspecified"))
    )
    (net (code "68") (name "unconnected-(ESP-PadD34)") (class "Default")
      (node (ref "ESP") (pin "D34") (pinfunction "D34_D34") (pintype "unspecified"))
    )
    (net (code "69") (name "unconnected-(ESP-PadD35)") (class "Default")
      (node (ref "ESP") (pin "D35") (pinfunction "D35_D35") (pintype "unspecified"))
    )
    (net (code "70") (name "unconnected-(ESP-PadEN)") (class "Default")
      (node (ref "ESP") (pin "EN") (pinfunction "EN_EN") (pintype "unspecified"))
    )
    (net (code "71") (name "unconnected-(ESP-PadRX0)") (class "Default")
      (node (ref "ESP") (pin "RX0") (pinfunction "RX0_RX0") (pintype "unspecified"))
    )
    (net (code "72") (name "unconnected-(ESP-PadTX0)") (class "Default")
      (node (ref "ESP") (pin "TX0") (pinfunction "TX0_TX0") (pintype "unspecified"))
    )
    (net (code "73") (name "unconnected-(LAN-3V3-Pad10)") (class "Default")
      (node (ref "LAN") (pin "10") (pinfunction "3V3_10") (pintype "unspecified"))
    )
    (net (code "74") (name "unconnected-(LAN-GND-Pad1)") (class "Default")
      (node (ref "LAN") (pin "1") (pinfunction "GND_1") (pintype "unspecified"))
    )
    (net (code "75") (name "unconnected-(LAN-GND-Pad2)") (class "Default")
      (node (ref "LAN") (pin "2") (pinfunction "GND_2") (pintype "unspecified"))
    )
    (net (code "76") (name "unconnected-(LAN-INT-Pad6)") (class "Default")
      (node (ref "LAN") (pin "6") (pinfunction "INT_6") (pintype "unspecified"))
    )
    (net (code "77") (name "unconnected-(LAN-NC-Pad9)") (class "Default")
      (node (ref "LAN") (pin "9") (pinfunction "NC_9") (pintype "unspecified"))
    )
    (net (code "78") (name "unconnected-(LAN-RST-Pad8)") (class "Default")
      (node (ref "LAN") (pin "8") (pinfunction "RST_8") (pintype "unspecified"))
    )
    (net (code "79") (name "unconnected-(LED1-A-Pad2)") (class "Default")
      (node (ref "LED1") (pin "2") (pinfunction "A_2") (pintype "unspecified"))
    )
    (net (code "80") (name "unconnected-(LED1-K-Pad1)") (class "Default")
      (node (ref "LED1") (pin "1") (pinfunction "K_1") (pintype "unspecified"))
    )
  )
)
